# CF_FMC_ABC.net
KiCad netlist of a schematic drawn in Altium Designer
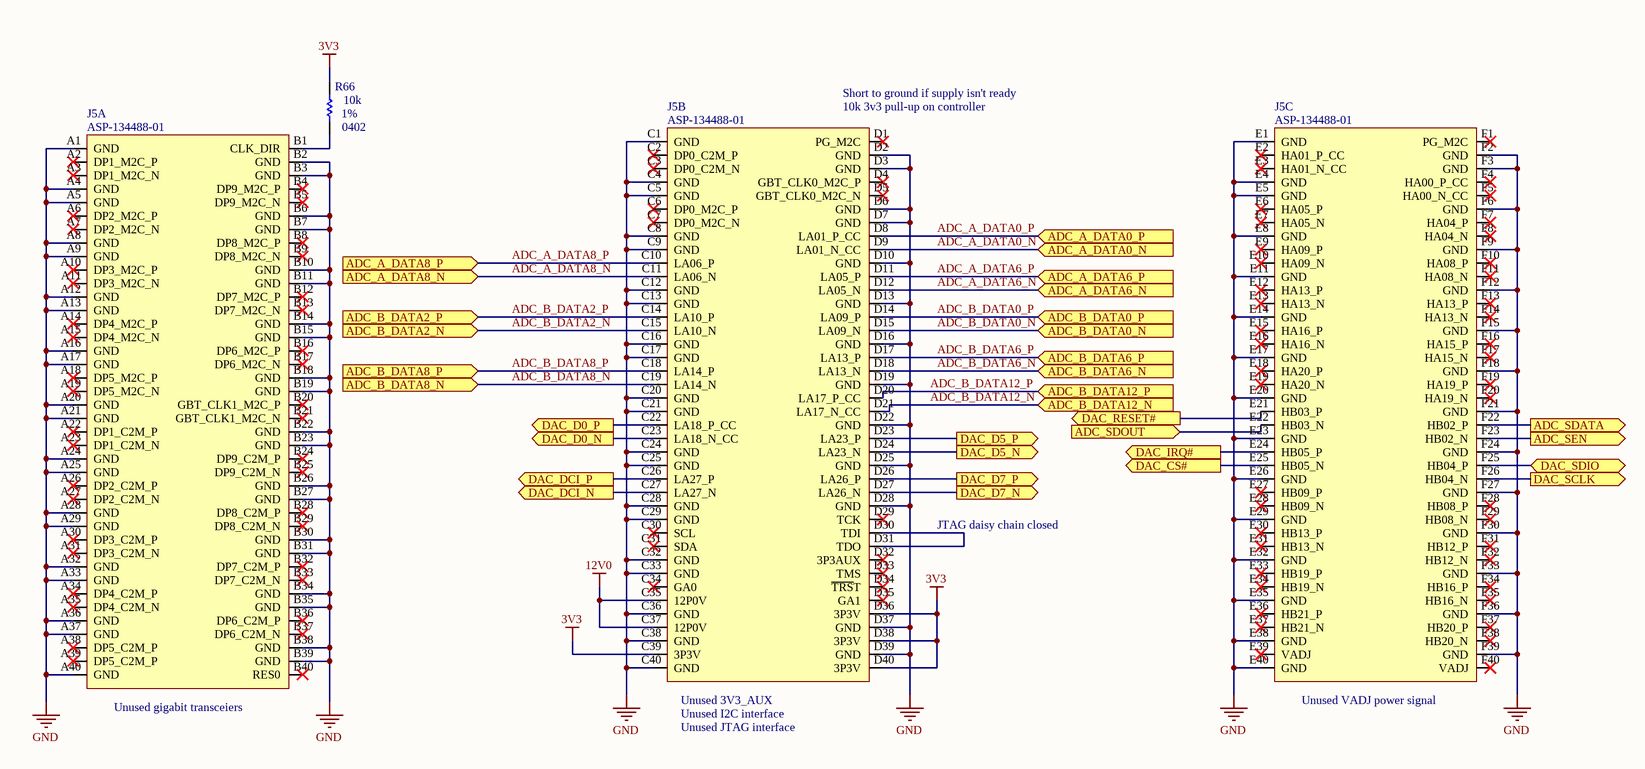
[diagram p0: CF_FMC_ABC.SchDoc]

(export (version "E")
  (design (tool "Eeschema 10.0.6"))
  (components
    (comp (ref "J5")
      (value "ASP-134488-01")
      (footprint "CONN_SAMTEC_ASP-134488-01")
      (description "CONN - VITA 57 MEZZ MALE (DAUGHTERBOARD) HIGH DENSITY - SMD-400")
      (fields
        (field (name "VOLTAGE") "240VAC")
        (field (name "MFG") "Samtec")
        (field (name "CREATEDBY") "Jonathan Bouchard")
      )
      (libsource (lib "S7CAS_Lib2019_REV1_00") (part "CONN_SAMTEC_ASP-134488-01"))
    )
    (comp (ref "R66")
      (value "10k")
      (footprint "RES_0402")
      (description "RES - 0402")
      (fields
        (field (name "VOLTAGE") "50V")
        (field (name "POWER") "1/16W")
        (field (name "PACKAGE") "0402")
        (field (name "PRECISION") "1%")
        (field (name "CREATEDBY") "Jonathan Bouchard")
      )
      (libsource (lib "S7CAS_Lib2019_REV1_00") (part "RES - 0402"))
    )
  )
  (nets
    (net (code "1") (name "/ADC_A_DATA0_N") (class "Default")
      (node (ref "J5") (pin "D9") (pinfunction "LA01_N_CC_D9") (pintype "passive"))
    )
    (net (code "2") (name "/ADC_A_DATA0_P") (class "Default")
      (node (ref "J5") (pin "D8") (pinfunction "LA01_P_CC_D8") (pintype "passive"))
    )
    (net (code "3") (name "/ADC_A_DATA6_N") (class "Default")
      (node (ref "J5") (pin "D12") (pinfunction "LA05_N_D12") (pintype "passive"))
    )
    (net (code "4") (name "/ADC_A_DATA6_P") (class "Default")
      (node (ref "J5") (pin "D11") (pinfunction "LA05_P_D11") (pintype "passive"))
    )
    (net (code "5") (name "/ADC_A_DATA8_N") (class "Default")
      (node (ref "J5") (pin "C11") (pinfunction "LA06_N_C11") (pintype "passive"))
    )
    (net (code "6") (name "/ADC_A_DATA8_P") (class "Default")
      (node (ref "J5") (pin "C10") (pinfunction "LA06_P_C10") (pintype "passive"))
    )
    (net (code "7") (name "/ADC_B_DATA0_N") (class "Default")
      (node (ref "J5") (pin "D15") (pinfunction "LA09_N_D15") (pintype "passive"))
    )
    (net (code "8") (name "/ADC_B_DATA0_P") (class "Default")
      (node (ref "J5") (pin "D14") (pinfunction "LA09_P_D14") (pintype "passive"))
    )
    (net (code "9") (name "/ADC_B_DATA2_N") (class "Default")
      (node (ref "J5") (pin "C15") (pinfunction "LA10_N_C15") (pintype "passive"))
    )
    (net (code "10") (name "/ADC_B_DATA2_P") (class "Default")
      (node (ref "J5") (pin "C14") (pinfunction "LA10_P_C14") (pintype "passive"))
    )
    (net (code "11") (name "/ADC_B_DATA6_N") (class "Default")
      (node (ref "J5") (pin "D18") (pinfunction "LA13_N_D18") (pintype "passive"))
    )
    (net (code "12") (name "/ADC_B_DATA6_P") (class "Default")
      (node (ref "J5") (pin "D17") (pinfunction "LA13_P_D17") (pintype "passive"))
    )
    (net (code "13") (name "/ADC_B_DATA8_N") (class "Default")
      (node (ref "J5") (pin "C19") (pinfunction "LA14_N_C19") (pintype "passive"))
    )
    (net (code "14") (name "/ADC_B_DATA8_P") (class "Default")
      (node (ref "J5") (pin "C18") (pinfunction "LA14_P_C18") (pintype "passive"))
    )
    (net (code "15") (name "/ADC_B_DATA12_N") (class "Default")
      (node (ref "J5") (pin "D21") (pinfunction "LA17_N_CC_D21") (pintype "passive"))
    )
    (net (code "16") (name "/ADC_B_DATA12_P") (class "Default")
      (node (ref "J5") (pin "D20") (pinfunction "LA17_P_CC_D20") (pintype "passive"))
    )
    (net (code "17") (name "/ADC_SDATA") (class "Default")
      (node (ref "J5") (pin "F22") (pinfunction "HB02_P_F22") (pintype "passive"))
    )
    (net (code "18") (name "/ADC_SDOUT") (class "Default")
      (node (ref "J5") (pin "E22") (pinfunction "HB03_N_E22") (pintype "passive"))
    )
    (net (code "19") (name "/ADC_SEN") (class "Default")
      (node (ref "J5") (pin "F23") (pinfunction "HB02_N_F23") (pintype "passive"))
    )
    (net (code "20") (name "/DAC_CS#") (class "Default")
      (node (ref "J5") (pin "E25") (pinfunction "HB05_N_E25") (pintype "passive"))
    )
    (net (code "21") (name "/DAC_D0_N") (class "Default")
      (node (ref "J5") (pin "C23") (pinfunction "LA18_N_CC_C23") (pintype "passive"))
    )
    (net (code "22") (name "/DAC_D0_P") (class "Default")
      (node (ref "J5") (pin "C22") (pinfunction "LA18_P_CC_C22") (pintype "passive"))
    )
    (net (code "23") (name "/DAC_D5_N") (class "Default")
      (node (ref "J5") (pin "D24") (pinfunction "LA23_N_D24") (pintype "passive"))
    )
    (net (code "24") (name "/DAC_D5_P") (class "Default")
      (node (ref "J5") (pin "D23") (pinfunction "LA23_P_D23") (pintype "passive"))
    )
    (net (code "25") (name "/DAC_D7_N") (class "Default")
      (node (ref "J5") (pin "D27") (pinfunction "LA26_N_D27") (pintype "passive"))
    )
    (net (code "26") (name "/DAC_D7_P") (class "Default")
      (node (ref "J5") (pin "D26") (pinfunction "LA26_P_D26") (pintype "passive"))
    )
    (net (code "27") (name "/DAC_DCI_N") (class "Default")
      (node (ref "J5") (pin "C27") (pinfunction "LA27_N_C27") (pintype "passive"))
    )
    (net (code "28") (name "/DAC_DCI_P") (class "Default")
      (node (ref "J5") (pin "C26") (pinfunction "LA27_P_C26") (pintype "passive"))
    )
    (net (code "29") (name "/DAC_IRQ#") (class "Default")
      (node (ref "J5") (pin "E24") (pinfunction "HB05_P_E24") (pintype "passive"))
    )
    (net (code "30") (name "/DAC_RESET#") (class "Default")
      (node (ref "J5") (pin "E21") (pinfunction "HB03_P_E21") (pintype "passive"))
    )
    (net (code "31") (name "/DAC_SCLK") (class "Default")
      (node (ref "J5") (pin "F26") (pinfunction "HB04_N_F26") (pintype "passive"))
    )
    (net (code "32") (name "/DAC_SDIO") (class "Default")
      (node (ref "J5") (pin "F25") (pinfunction "HB04_P_F25") (pintype "passive"))
    )
    (net (code "33") (name "3V3") (class "Default")
      (node (ref "J5") (pin "C39") (pinfunction "3P3V_C39") (pintype "passive"))
      (node (ref "J5") (pin "D36") (pinfunction "3P3V_D36") (pintype "passive"))
      (node (ref "J5") (pin "D38") (pinfunction "3P3V_D38") (pintype "passive"))
      (node (ref "J5") (pin "D40") (pinfunction "3P3V_D40") (pintype "passive"))
      (node (ref "R66") (pin "2") (pinfunction "2_2") (pintype "passive"))
    )
    (net (code "34") (name "12V0") (class "Default")
      (node (ref "J5") (pin "C35") (pinfunction "12P0V_C35") (pintype "passive"))
      (node (ref "J5") (pin "C37") (pinfunction "12P0V_C37") (pintype "passive"))
    )
    (net (code "35") (name "GND") (class "Default")
      (node (ref "J5") (pin "A1") (pinfunction "GND_A1") (pintype "passive"))
      (node (ref "J5") (pin "A12") (pinfunction "GND_A12") (pintype "passive"))
      (node (ref "J5") (pin "A13") (pinfunction "GND_A13") (pintype "passive"))
      (node (ref "J5") (pin "A16") (pinfunction "GND_A16") (pintype "passive"))
      (node (ref "J5") (pin "A17") (pinfunction "GND_A17") (pintype "passive"))
      (node (ref "J5") (pin "A20") (pinfunction "GND_A20") (pintype "passive"))
      (node (ref "J5") (pin "A21") (pinfunction "GND_A21") (pintype "passive"))
      (node (ref "J5") (pin "A24") (pinfunction "GND_A24") (pintype "passive"))
      (node (ref "J5") (pin "A25") (pinfunction "GND_A25") (pintype "passive"))
      (node (ref "J5") (pin "A28") (pinfunction "GND_A28") (pintype "passive"))
      (node (ref "J5") (pin "A29") (pinfunction "GND_A29") (pintype "passive"))
      (node (ref "J5") (pin "A32") (pinfunction "GND_A32") (pintype "passive"))
      (node (ref "J5") (pin "A33") (pinfunction "GND_A33") (pintype "passive"))
      (node (ref "J5") (pin "A36") (pinfunction "GND_A36") (pintype "passive"))
      (node (ref "J5") (pin "A37") (pinfunction "GND_A37") (pintype "passive"))
      (node (ref "J5") (pin "A4") (pinfunction "GND_A4") (pintype "passive"))
      (node (ref "J5") (pin "A40") (pinfunction "GND_A40") (pintype "passive"))
      (node (ref "J5") (pin "A5") (pinfunction "GND_A5") (pintype "passive"))
      (node (ref "J5") (pin "A8") (pinfunction "GND_A8") (pintype "passive"))
      (node (ref "J5") (pin "A9") (pinfunction "GND_A9") (pintype "passive"))
      (node (ref "J5") (pin "B10") (pinfunction "GND_B10") (pintype "passive"))
      (node (ref "J5") (pin "B11") (pinfunction "GND_B11") (pintype "passive"))
      (node (ref "J5") (pin "B14") (pinfunction "GND_B14") (pintype "passive"))
      (node (ref "J5") (pin "B15") (pinfunction "GND_B15") (pintype "passive"))
      (node (ref "J5") (pin "B18") (pinfunction "GND_B18") (pintype "passive"))
      (node (ref "J5") (pin "B19") (pinfunction "GND_B19") (pintype "passive"))
      (node (ref "J5") (pin "B2") (pinfunction "GND_B2") (pintype "passive"))
      (node (ref "J5") (pin "B22") (pinfunction "GND_B22") (pintype "passive"))
      (node (ref "J5") (pin "B23") (pinfunction "GND_B23") (pintype "passive"))
      (node (ref "J5") (pin "B26") (pinfunction "GND_B26") (pintype "passive"))
      (node (ref "J5") (pin "B27") (pinfunction "GND_B27") (pintype "passive"))
      (node (ref "J5") (pin "B3") (pinfunction "GND_B3") (pintype "passive"))
      (node (ref "J5") (pin "B30") (pinfunction "GND_B30") (pintype "passive"))
      (node (ref "J5") (pin "B31") (pinfunction "GND_B31") (pintype "passive"))
      (node (ref "J5") (pin "B34") (pinfunction "GND_B34") (pintype "passive"))
      (node (ref "J5") (pin "B35") (pinfunction "GND_B35") (pintype "passive"))
      (node (ref "J5") (pin "B38") (pinfunction "GND_B38") (pintype "passive"))
      (node (ref "J5") (pin "B39") (pinfunction "GND_B39") (pintype "passive"))
      (node (ref "J5") (pin "B6") (pinfunction "GND_B6") (pintype "passive"))
      (node (ref "J5") (pin "B7") (pinfunction "GND_B7") (pintype "passive"))
      (node (ref "J5") (pin "C1") (pinfunction "GND_C1") (pintype "passive"))
      (node (ref "J5") (pin "C12") (pinfunction "GND_C12") (pintype "passive"))
      (node (ref "J5") (pin "C13") (pinfunction "GND_C13") (pintype "passive"))
      (node (ref "J5") (pin "C16") (pinfunction "GND_C16") (pintype "passive"))
      (node (ref "J5") (pin "C17") (pinfunction "GND_C17") (pintype "passive"))
      (node (ref "J5") (pin "C20") (pinfunction "GND_C20") (pintype "passive"))
      (node (ref "J5") (pin "C21") (pinfunction "GND_C21") (pintype "passive"))
      (node (ref "J5") (pin "C24") (pinfunction "GND_C24") (pintype "passive"))
      (node (ref "J5") (pin "C25") (pinfunction "GND_C25") (pintype "passive"))
      (node (ref "J5") (pin "C28") (pinfunction "GND_C28") (pintype "passive"))
      (node (ref "J5") (pin "C29") (pinfunction "GND_C29") (pintype "passive"))
      (node (ref "J5") (pin "C32") (pinfunction "GND_C32") (pintype "passive"))
      (node (ref "J5") (pin "C33") (pinfunction "GND_C33") (pintype "passive"))
      (node (ref "J5") (pin "C36") (pinfunction "GND_C36") (pintype "passive"))
      (node (ref "J5") (pin "C38") (pinfunction "GND_C38") (pintype "passive"))
      (node (ref "J5") (pin "C4") (pinfunction "GND_C4") (pintype "passive"))
      (node (ref "J5") (pin "C40") (pinfunction "GND_C40") (pintype "passive"))
      (node (ref "J5") (pin "C5") (pinfunction "GND_C5") (pintype "passive"))
      (node (ref "J5") (pin "C8") (pinfunction "GND_C8") (pintype "passive"))
      (node (ref "J5") (pin "C9") (pinfunction "GND_C9") (pintype "passive"))
      (node (ref "J5") (pin "D10") (pinfunction "GND_D10") (pintype "passive"))
      (node (ref "J5") (pin "D13") (pinfunction "GND_D13") (pintype "passive"))
      (node (ref "J5") (pin "D16") (pinfunction "GND_D16") (pintype "passive"))
      (node (ref "J5") (pin "D19") (pinfunction "GND_D19") (pintype "passive"))
      (node (ref "J5") (pin "D2") (pinfunction "GND_D2") (pintype "passive"))
      (node (ref "J5") (pin "D22") (pinfunction "GND_D22") (pintype "passive"))
      (node (ref "J5") (pin "D25") (pinfunction "GND_D25") (pintype "passive"))
      (node (ref "J5") (pin "D28") (pinfunction "GND_D28") (pintype "passive"))
      (node (ref "J5") (pin "D3") (pinfunction "GND_D3") (pintype "passive"))
      (node (ref "J5") (pin "D37") (pinfunction "GND_D37") (pintype "passive"))
      (node (ref "J5") (pin "D39") (pinfunction "GND_D39") (pintype "passive"))
      (node (ref "J5") (pin "D6") (pinfunction "GND_D6") (pintype "passive"))
      (node (ref "J5") (pin "D7") (pinfunction "GND_D7") (pintype "passive"))
      (node (ref "J5") (pin "E1") (pinfunction "GND_E1") (pintype "passive"))
      (node (ref "J5") (pin "E11") (pinfunction "GND_E11") (pintype "passive"))
      (node (ref "J5") (pin "E14") (pinfunction "GND_E14") (pintype "passive"))
      (node (ref "J5") (pin "E17") (pinfunction "GND_E17") (pintype "passive"))
      (node (ref "J5") (pin "E20") (pinfunction "GND_E20") (pintype "passive"))
      (node (ref "J5") (pin "E23") (pinfunction "GND_E23") (pintype "passive"))
      (node (ref "J5") (pin "E26") (pinfunction "GND_E26") (pintype "passive"))
      (node (ref "J5") (pin "E29") (pinfunction "GND_E29") (pintype "passive"))
      (node (ref "J5") (pin "E32") (pinfunction "GND_E32") (pintype "passive"))
      (node (ref "J5") (pin "E35") (pinfunction "GND_E35") (pintype "passive"))
      (node (ref "J5") (pin "E38") (pinfunction "GND_E38") (pintype "passive"))
      (node (ref "J5") (pin "E4") (pinfunction "GND_E4") (pintype "passive"))
      (node (ref "J5") (pin "E40") (pinfunction "GND_E40") (pintype "passive"))
      (node (ref "J5") (pin "E5") (pinfunction "GND_E5") (pintype "passive"))
      (node (ref "J5") (pin "E8") (pinfunction "GND_E8") (pintype "passive"))
      (node (ref "J5") (pin "F12") (pinfunction "GND_F12") (pintype "passive"))
      (node (ref "J5") (pin "F15") (pinfunction "GND_F15") (pintype "passive"))
      (node (ref "J5") (pin "F18") (pinfunction "GND_F18") (pintype "passive"))
      (node (ref "J5") (pin "F2") (pinfunction "GND_F2") (pintype "passive"))
      (node (ref "J5") (pin "F21") (pinfunction "GND_F21") (pintype "passive"))
      (node (ref "J5") (pin "F24") (pinfunction "GND_F24") (pintype "passive"))
      (node (ref "J5") (pin "F27") (pinfunction "GND_F27") (pintype "passive"))
      (node (ref "J5") (pin "F3") (pinfunction "GND_F3") (pintype "passive"))
      (node (ref "J5") (pin "F30") (pinfunction "GND_F30") (pintype "passive"))
      (node (ref "J5") (pin "F33") (pinfunction "GND_F33") (pintype "passive"))
      (node (ref "J5") (pin "F36") (pinfunction "GND_F36") (pintype "passive"))
      (node (ref "J5") (pin "F39") (pinfunction "GND_F39") (pintype "passive"))
      (node (ref "J5") (pin "F6") (pinfunction "GND_F6") (pintype "passive"))
      (node (ref "J5") (pin "F9") (pinfunction "GND_F9") (pintype "passive"))
    )
    (net (code "36") (name "Net-(J5A-CLK_DIR)") (class "Default")
      (node (ref "J5") (pin "B1") (pinfunction "CLK_DIR_B1") (pintype "passive"))
      (node (ref "R66") (pin "1") (pinfunction "1_1") (pintype "passive"))
    )
    (net (code "37") (name "Net-(J5B-TDI)") (class "Default")
      (node (ref "J5") (pin "D30") (pinfunction "TDI_D30") (pintype "passive"))
      (node (ref "J5") (pin "D31") (pinfunction "TDO_D31") (pintype "passive"))
    )
    (net (code "38") (name "unconnected-(J5A-DP1_C2M_N-PadA23)") (class "Default")
      (node (ref "J5") (pin "A23") (pinfunction "DP1_C2M_N_A23") (pintype "passive+no_connect"))
    )
    (net (code "39") (name "unconnected-(J5A-DP1_C2M_P-PadA22)") (class "Default")
      (node (ref "J5") (pin "A22") (pinfunction "DP1_C2M_P_A22") (pintype "passive+no_connect"))
    )
    (net (code "40") (name "unconnected-(J5A-DP1_M2C_N-PadA3)") (class "Default")
      (node (ref "J5") (pin "A3") (pinfunction "DP1_M2C_N_A3") (pintype "passive+no_connect"))
    )
    (net (code "41") (name "unconnected-(J5A-DP1_M2C_P-PadA2)") (class "Default")
      (node (ref "J5") (pin "A2") (pinfunction "DP1_M2C_P_A2") (pintype "passive+no_connect"))
    )
    (net (code "42") (name "unconnected-(J5A-DP2_C2M_N-PadA27)") (class "Default")
      (node (ref "J5") (pin "A27") (pinfunction "DP2_C2M_N_A27") (pintype "passive+no_connect"))
    )
    (net (code "43") (name "unconnected-(J5A-DP2_C2M_P-PadA26)") (class "Default")
      (node (ref "J5") (pin "A26") (pinfunction "DP2_C2M_P_A26") (pintype "passive+no_connect"))
    )
    (net (code "44") (name "unconnected-(J5A-DP2_M2C_N-PadA7)") (class "Default")
      (node (ref "J5") (pin "A7") (pinfunction "DP2_M2C_N_A7") (pintype "passive+no_connect"))
    )
    (net (code "45") (name "unconnected-(J5A-DP2_M2C_P-PadA6)") (class "Default")
      (node (ref "J5") (pin "A6") (pinfunction "DP2_M2C_P_A6") (pintype "passive+no_connect"))
    )
    (net (code "46") (name "unconnected-(J5A-DP3_C2M_N-PadA31)") (class "Default")
      (node (ref "J5") (pin "A31") (pinfunction "DP3_C2M_N_A31") (pintype "passive+no_connect"))
    )
    (net (code "47") (name "unconnected-(J5A-DP3_C2M_P-PadA30)") (class "Default")
      (node (ref "J5") (pin "A30") (pinfunction "DP3_C2M_P_A30") (pintype "passive+no_connect"))
    )
    (net (code "48") (name "unconnected-(J5A-DP3_M2C_N-PadA11)") (class "Default")
      (node (ref "J5") (pin "A11") (pinfunction "DP3_M2C_N_A11") (pintype "passive+no_connect"))
    )
    (net (code "49") (name "unconnected-(J5A-DP3_M2C_P-PadA10)") (class "Default")
      (node (ref "J5") (pin "A10") (pinfunction "DP3_M2C_P_A10") (pintype "passive+no_connect"))
    )
    (net (code "50") (name "unconnected-(J5A-DP4_C2M_N-PadA35)") (class "Default")
      (node (ref "J5") (pin "A35") (pinfunction "DP4_C2M_N_A35") (pintype "passive+no_connect"))
    )
    (net (code "51") (name "unconnected-(J5A-DP4_C2M_P-PadA34)") (class "Default")
      (node (ref "J5") (pin "A34") (pinfunction "DP4_C2M_P_A34") (pintype "passive+no_connect"))
    )
    (net (code "52") (name "unconnected-(J5A-DP4_M2C_N-PadA15)") (class "Default")
      (node (ref "J5") (pin "A15") (pinfunction "DP4_M2C_N_A15") (pintype "passive+no_connect"))
    )
    (net (code "53") (name "unconnected-(J5A-DP4_M2C_P-PadA14)") (class "Default")
      (node (ref "J5") (pin "A14") (pinfunction "DP4_M2C_P_A14") (pintype "passive+no_connect"))
    )
    (net (code "54") (name "unconnected-(J5A-DP5_C2M_P-PadA38)") (class "Default")
      (node (ref "J5") (pin "A38") (pinfunction "DP5_C2M_P_A38") (pintype "passive+no_connect"))
    )
    (net (code "55") (name "unconnected-(J5A-DP5_C2M_P-PadA39)") (class "Default")
      (node (ref "J5") (pin "A39") (pinfunction "DP5_C2M_P_A39") (pintype "passive+no_connect"))
    )
    (net (code "56") (name "unconnected-(J5A-DP5_M2C_N-PadA19)") (class "Default")
      (node (ref "J5") (pin "A19") (pinfunction "DP5_M2C_N_A19") (pintype "passive+no_connect"))
    )
    (net (code "57") (name "unconnected-(J5A-DP5_M2C_P-PadA18)") (class "Default")
      (node (ref "J5") (pin "A18") (pinfunction "DP5_M2C_P_A18") (pintype "passive+no_connect"))
    )
    (net (code "58") (name "unconnected-(J5A-DP6_C2M_N-PadB37)") (class "Default")
      (node (ref "J5") (pin "B37") (pinfunction "DP6_C2M_N_B37") (pintype "passive+no_connect"))
    )
    (net (code "59") (name "unconnected-(J5A-DP6_C2M_P-PadB36)") (class "Default")
      (node (ref "J5") (pin "B36") (pinfunction "DP6_C2M_P_B36") (pintype "passive+no_connect"))
    )
    (net (code "60") (name "unconnected-(J5A-DP6_M2C_N-PadB17)") (class "Default")
      (node (ref "J5") (pin "B17") (pinfunction "DP6_M2C_N_B17") (pintype "passive+no_connect"))
    )
    (net (code "61") (name "unconnected-(J5A-DP6_M2C_P-PadB16)") (class "Default")
      (node (ref "J5") (pin "B16") (pinfunction "DP6_M2C_P_B16") (pintype "passive+no_connect"))
    )
    (net (code "62") (name "unconnected-(J5A-DP7_C2M_N-PadB33)") (class "Default")
      (node (ref "J5") (pin "B33") (pinfunction "DP7_C2M_N_B33") (pintype "passive+no_connect"))
    )
    (net (code "63") (name "unconnected-(J5A-DP7_C2M_P-PadB32)") (class "Default")
      (node (ref "J5") (pin "B32") (pinfunction "DP7_C2M_P_B32") (pintype "passive+no_connect"))
    )
    (net (code "64") (name "unconnected-(J5A-DP7_M2C_N-PadB13)") (class "Default")
      (node (ref "J5") (pin "B13") (pinfunction "DP7_M2C_N_B13") (pintype "passive+no_connect"))
    )
    (net (code "65") (name "unconnected-(J5A-DP7_M2C_P-PadB12)") (class "Default")
      (node (ref "J5") (pin "B12") (pinfunction "DP7_M2C_P_B12") (pintype "passive+no_connect"))
    )
    (net (code "66") (name "unconnected-(J5A-DP8_C2M_N-PadB29)") (class "Default")
      (node (ref "J5") (pin "B29") (pinfunction "DP8_C2M_N_B29") (pintype "passive+no_connect"))
    )
    (net (code "67") (name "unconnected-(J5A-DP8_C2M_P-PadB28)") (class "Default")
      (node (ref "J5") (pin "B28") (pinfunction "DP8_C2M_P_B28") (pintype "passive+no_connect"))
    )
    (net (code "68") (name "unconnected-(J5A-DP8_M2C_N-PadB9)") (class "Default")
      (node (ref "J5") (pin "B9") (pinfunction "DP8_M2C_N_B9") (pintype "passive+no_connect"))
    )
    (net (code "69") (name "unconnected-(J5A-DP8_M2C_P-PadB8)") (class "Default")
      (node (ref "J5") (pin "B8") (pinfunction "DP8_M2C_P_B8") (pintype "passive+no_connect"))
    )
    (net (code "70") (name "unconnected-(J5A-DP9_C2M_N-PadB25)") (class "Default")
      (node (ref "J5") (pin "B25") (pinfunction "DP9_C2M_N_B25") (pintype "passive+no_connect"))
    )
    (net (code "71") (name "unconnected-(J5A-DP9_C2M_P-PadB24)") (class "Default")
      (node (ref "J5") (pin "B24") (pinfunction "DP9_C2M_P_B24") (pintype "passive+no_connect"))
    )
    (net (code "72") (name "unconnected-(J5A-DP9_M2C_N-PadB5)") (class "Default")
      (node (ref "J5") (pin "B5") (pinfunction "DP9_M2C_N_B5") (pintype "passive+no_connect"))
    )
    (net (code "73") (name "unconnected-(J5A-DP9_M2C_P-PadB4)") (class "Default")
      (node (ref "J5") (pin "B4") (pinfunction "DP9_M2C_P_B4") (pintype "passive+no_connect"))
    )
    (net (code "74") (name "unconnected-(J5A-GBT_CLK1_M2C_N-PadB21)") (class "Default")
      (node (ref "J5") (pin "B21") (pinfunction "GBT_CLK1_M2C_N_B21") (pintype "passive+no_connect"))
    )
    (net (code "75") (name "unconnected-(J5A-GBT_CLK1_M2C_P-PadB20)") (class "Default")
      (node (ref "J5") (pin "B20") (pinfunction "GBT_CLK1_M2C_P_B20") (pintype "passive+no_connect"))
    )
    (net (code "76") (name "unconnected-(J5A-RES0-PadB40)") (class "Default")
      (node (ref "J5") (pin "B40") (pinfunction "RES0_B40") (pintype "passive+no_connect"))
    )
    (net (code "77") (name "unconnected-(J5B-3P3AUX-PadD32)") (class "Default")
      (node (ref "J5") (pin "D32") (pinfunction "3P3AUX_D32") (pintype "passive+no_connect"))
    )
    (net (code "78") (name "unconnected-(J5B-DP0_C2M_N-PadC3)") (class "Default")
      (node (ref "J5") (pin "C3") (pinfunction "DP0_C2M_N_C3") (pintype "passive+no_connect"))
    )
    (net (code "79") (name "unconnected-(J5B-DP0_C2M_P-PadC2)") (class "Default")
      (node (ref "J5") (pin "C2") (pinfunction "DP0_C2M_P_C2") (pintype "passive+no_connect"))
    )
    (net (code "80") (name "unconnected-(J5B-DP0_M2C_N-PadC7)") (class "Default")
      (node (ref "J5") (pin "C7") (pinfunction "DP0_M2C_N_C7") (pintype "passive+no_connect"))
    )
    (net (code "81") (name "unconnected-(J5B-DP0_M2C_P-PadC6)") (class "Default")
      (node (ref "J5") (pin "C6") (pinfunction "DP0_M2C_P_C6") (pintype "passive+no_connect"))
    )
    (net (code "82") (name "unconnected-(J5B-GA0-PadC34)") (class "Default")
      (node (ref "J5") (pin "C34") (pinfunction "GA0_C34") (pintype "passive+no_connect"))
    )
    (net (code "83") (name "unconnected-(J5B-GA1-PadD35)") (class "Default")
      (node (ref "J5") (pin "D35") (pinfunction "GA1_D35") (pintype "passive+no_connect"))
    )
    (net (code "84") (name "unconnected-(J5B-GBT_CLK0_M2C_N-PadD5)") (class "Default")
      (node (ref "J5") (pin "D5") (pinfunction "GBT_CLK0_M2C_N_D5") (pintype "passive+no_connect"))
    )
    (net (code "85") (name "unconnected-(J5B-GBT_CLK0_M2C_P-PadD4)") (class "Default")
      (node (ref "J5") (pin "D4") (pinfunction "GBT_CLK0_M2C_P_D4") (pintype "passive+no_connect"))
    )
    (net (code "86") (name "unconnected-(J5B-PG_M2C-PadD1)") (class "Default")
      (node (ref "J5") (pin "D1") (pinfunction "PG_M2C_D1") (pintype "passive+no_connect"))
    )
    (net (code "87") (name "unconnected-(J5B-SCL-PadC30)") (class "Default")
      (node (ref "J5") (pin "C30") (pinfunction "SCL_C30") (pintype "passive+no_connect"))
    )
    (net (code "88") (name "unconnected-(J5B-SDA-PadC31)") (class "Default")
      (node (ref "J5") (pin "C31") (pinfunction "SDA_C31") (pintype "passive+no_connect"))
    )
    (net (code "89") (name "unconnected-(J5B-TCK-PadD29)") (class "Default")
      (node (ref "J5") (pin "D29") (pinfunction "TCK_D29") (pintype "passive+no_connect"))
    )
    (net (code "90") (name "unconnected-(J5B-TMS-PadD33)") (class "Default")
      (node (ref "J5") (pin "D33") (pinfunction "TMS_D33") (pintype "passive+no_connect"))
    )
    (net (code "91") (name "unconnected-(J5B-~{TRS}T-PadD34)") (class "Default")
      (node (ref "J5") (pin "D34") (pinfunction "~{TRS}T_D34") (pintype "passive+no_connect"))
    )
    (net (code "92") (name "unconnected-(J5C-HA00_N_CC-PadF5)") (class "Default")
      (node (ref "J5") (pin "F5") (pinfunction "HA00_N_CC_F5") (pintype "passive+no_connect"))
    )
    (net (code "93") (name "unconnected-(J5C-HA00_P_CC-PadF4)") (class "Default")
      (node (ref "J5") (pin "F4") (pinfunction "HA00_P_CC_F4") (pintype "passive+no_connect"))
    )
    (net (code "94") (name "unconnected-(J5C-HA01_N_CC-PadE3)") (class "Default")
      (node (ref "J5") (pin "E3") (pinfunction "HA01_N_CC_E3") (pintype "passive+no_connect"))
    )
    (net (code "95") (name "unconnected-(J5C-HA01_P_CC-PadE2)") (class "Default")
      (node (ref "J5") (pin "E2") (pinfunction "HA01_P_CC_E2") (pintype "passive+no_connect"))
    )
    (net (code "96") (name "unconnected-(J5C-HA04_N-PadF8)") (class "Default")
      (node (ref "J5") (pin "F8") (pinfunction "HA04_N_F8") (pintype "passive+no_connect"))
    )
    (net (code "97") (name "unconnected-(J5C-HA04_P-PadF7)") (class "Default")
      (node (ref "J5") (pin "F7") (pinfunction "HA04_P_F7") (pintype "passive+no_connect"))
    )
    (net (code "98") (name "unconnected-(J5C-HA05_N-PadE7)") (class "Default")
      (node (ref "J5") (pin "E7") (pinfunction "HA05_N_E7") (pintype "passive+no_connect"))
    )
    (net (code "99") (name "unconnected-(J5C-HA05_P-PadE6)") (class "Default")
      (node (ref "J5") (pin "E6") (pinfunction "HA05_P_E6") (pintype "passive+no_connect"))
    )
    (net (code "100") (name "unconnected-(J5C-HA08_N-PadF11)") (class "Default")
      (node (ref "J5") (pin "F11") (pinfunction "HA08_N_F11") (pintype "passive+no_connect"))
    )
    (net (code "101") (name "unconnected-(J5C-HA08_P-PadF10)") (class "Default")
      (node (ref "J5") (pin "F10") (pinfunction "HA08_P_F10") (pintype "passive+no_connect"))
    )
    (net (code "102") (name "unconnected-(J5C-HA09_N-PadE10)") (class "Default")
      (node (ref "J5") (pin "E10") (pinfunction "HA09_N_E10") (pintype "passive+no_connect"))
    )
    (net (code "103") (name "unconnected-(J5C-HA09_P-PadE9)") (class "Default")
      (node (ref "J5") (pin "E9") (pinfunction "HA09_P_E9") (pintype "passive+no_connect"))
    )
    (net (code "104") (name "unconnected-(J5C-HA12_N-PadF14)") (class "Default")
      (node (ref "J5") (pin "F14") (pinfunction "HA12_N_F14") (pintype "passive+no_connect"))
    )
    (net (code "105") (name "unconnected-(J5C-HA12_P-PadF13)") (class "Default")
      (node (ref "J5") (pin "F13") (pinfunction "HA12_P_F13") (pintype "passive+no_connect"))
    )
    (net (code "106") (name "unconnected-(J5C-HA13_N-PadE13)") (class "Default")
      (node (ref "J5") (pin "E13") (pinfunction "HA13_N_E13") (pintype "passive+no_connect"))
    )
    (net (code "107") (name "unconnected-(J5C-HA13_P-PadE12)") (class "Default")
      (node (ref "J5") (pin "E12") (pinfunction "HA13_P_E12") (pintype "passive+no_connect"))
    )
    (net (code "108") (name "unconnected-(J5C-HA15_N-PadF17)") (class "Default")
      (node (ref "J5") (pin "F17") (pinfunction "HA15_N_F17") (pintype "passive+no_connect"))
    )
    (net (code "109") (name "unconnected-(J5C-HA15_P-PadF16)") (class "Default")
      (node (ref "J5") (pin "F16") (pinfunction "HA15_P_F16") (pintype "passive+no_connect"))
    )
    (net (code "110") (name "unconnected-(J5C-HA16_N-PadE16)") (class "Default")
      (node (ref "J5") (pin "E16") (pinfunction "HA16_N_E16") (pintype "passive+no_connect"))
    )
    (net (code "111") (name "unconnected-(J5C-HA16_P-PadE15)") (class "Default")
      (node (ref "J5") (pin "E15") (pinfunction "HA16_P_E15") (pintype "passive+no_connect"))
    )
    (net (code "112") (name "unconnected-(J5C-HA19_N-PadF20)") (class "Default")
      (node (ref "J5") (pin "F20") (pinfunction "HA19_N_F20") (pintype "passive+no_connect"))
    )
    (net (code "113") (name "unconnected-(J5C-HA19_P-PadF19)") (class "Default")
      (node (ref "J5") (pin "F19") (pinfunction "HA19_P_F19") (pintype "passive+no_connect"))
    )
    (net (code "114") (name "unconnected-(J5C-HA20_N-PadE19)") (class "Default")
      (node (ref "J5") (pin "E19") (pinfunction "HA20_N_E19") (pintype "passive+no_connect"))
    )
    (net (code "115") (name "unconnected-(J5C-HA20_P-PadE18)") (class "Default")
      (node (ref "J5") (pin "E18") (pinfunction "HA20_P_E18") (pintype "passive+no_connect"))
    )
    (net (code "116") (name "unconnected-(J5C-HB08_N-PadF29)") (class "Default")
      (node (ref "J5") (pin "F29") (pinfunction "HB08_N_F29") (pintype "passive+no_connect"))
    )
    (net (code "117") (name "unconnected-(J5C-HB08_P-PadF28)") (class "Default")
      (node (ref "J5") (pin "F28") (pinfunction "HB08_P_F28") (pintype "passive+no_connect"))
    )
    (net (code "118") (name "unconnected-(J5C-HB09_N-PadE28)") (class "Default")
      (node (ref "J5") (pin "E28") (pinfunction "HB09_N_E28") (pintype "passive+no_connect"))
    )
    (net (code "119") (name "unconnected-(J5C-HB09_P-PadE27)") (class "Default")
      (node (ref "J5") (pin "E27") (pinfunction "HB09_P_E27") (pintype "passive+no_connect"))
    )
    (net (code "120") (name "unconnected-(J5C-HB12_N-PadF32)") (class "Default")
      (node (ref "J5") (pin "F32") (pinfunction "HB12_N_F32") (pintype "passive+no_connect"))
    )
    (net (code "121") (name "unconnected-(J5C-HB12_P-PadF31)") (class "Default")
      (node (ref "J5") (pin "F31") (pinfunction "HB12_P_F31") (pintype "passive+no_connect"))
    )
    (net (code "122") (name "unconnected-(J5C-HB13_N-PadE31)") (class "Default")
      (node (ref "J5") (pin "E31") (pinfunction "HB13_N_E31") (pintype "passive+no_connect"))
    )
    (net (code "123") (name "unconnected-(J5C-HB13_P-PadE30)") (class "Default")
      (node (ref "J5") (pin "E30") (pinfunction "HB13_P_E30") (pintype "passive+no_connect"))
    )
    (net (code "124") (name "unconnected-(J5C-HB16_N-PadF35)") (class "Default")
      (node (ref "J5") (pin "F35") (pinfunction "HB16_N_F35") (pintype "passive+no_connect"))
    )
    (net (code "125") (name "unconnected-(J5C-HB16_P-PadF34)") (class "Default")
      (node (ref "J5") (pin "F34") (pinfunction "HB16_P_F34") (pintype "passive+no_connect"))
    )
    (net (code "126") (name "unconnected-(J5C-HB19_N-PadE34)") (class "Default")
      (node (ref "J5") (pin "E34") (pinfunction "HB19_N_E34") (pintype "passive+no_connect"))
    )
    (net (code "127") (name "unconnected-(J5C-HB19_P-PadE33)") (class "Default")
      (node (ref "J5") (pin "E33") (pinfunction "HB19_P_E33") (pintype "passive+no_connect"))
    )
    (net (code "128") (name "unconnected-(J5C-HB20_N-PadF38)") (class "Default")
      (node (ref "J5") (pin "F38") (pinfunction "HB20_N_F38") (pintype "passive+no_connect"))
    )
    (net (code "129") (name "unconnected-(J5C-HB20_P-PadF37)") (class "Default")
      (node (ref "J5") (pin "F37") (pinfunction "HB20_P_F37") (pintype "passive+no_connect"))
    )
    (net (code "130") (name "unconnected-(J5C-HB21_N-PadE37)") (class "Default")
      (node (ref "J5") (pin "E37") (pinfunction "HB21_N_E37") (pintype "passive+no_connect"))
    )
    (net (code "131") (name "unconnected-(J5C-HB21_P-PadE36)") (class "Default")
      (node (ref "J5") (pin "E36") (pinfunction "HB21_P_E36") (pintype "passive+no_connect"))
    )
    (net (code "132") (name "unconnected-(J5C-PG_M2C-PadF1)") (class "Default")
      (node (ref "J5") (pin "F1") (pinfunction "PG_M2C_F1") (pintype "passive+no_connect"))
    )
    (net (code "133") (name "unconnected-(J5C-VADJ-PadE39)") (class "Default")
      (node (ref "J5") (pin "E39") (pinfunction "VADJ_E39") (pintype "passive+no_connect"))
    )
    (net (code "134") (name "unconnected-(J5C-VADJ-PadF40)") (class "Default")
      (node (ref "J5") (pin "F40") (pinfunction "VADJ_F40") (pintype "passive+no_connect"))
    )
  )
)
